# SCH__TX510__2025-04-04_-.net
KiCad netlist of a schematic drawn in Altium Designer
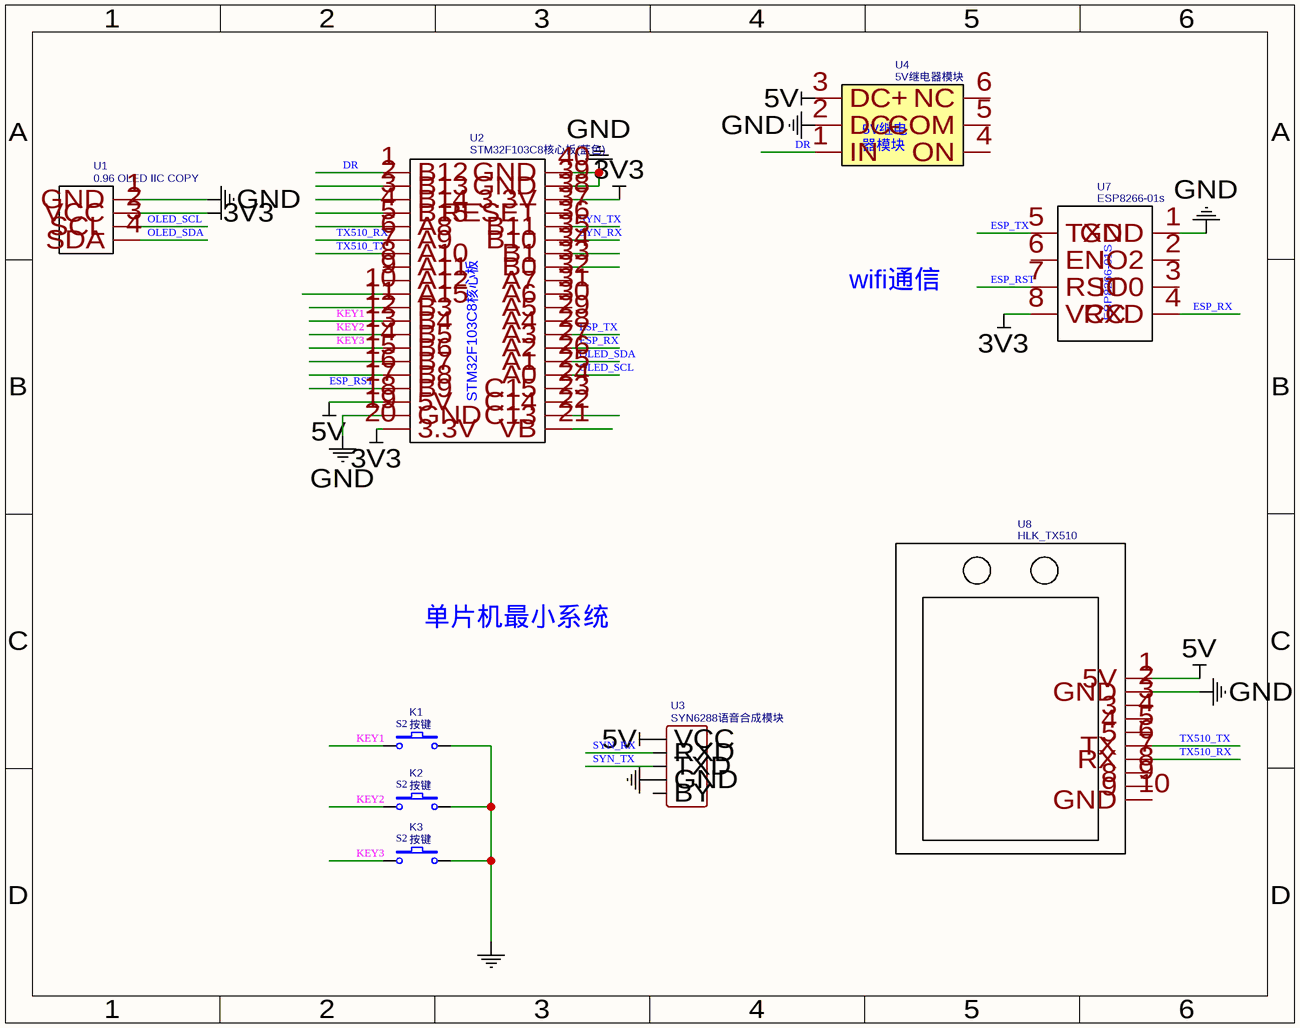
[diagram p0: SCH_人脸识别TX510和考勤_2025-04-04 - 副本.schdoc]

(export (version "E")
  (design (tool "Eeschema 10.0.6"))
  (components
    (comp (ref "K1")
      (value "按键")
      (fields (field (name "CONTRIBUTOR") "tongtongll"))
      (libsource (lib "altium-import") (part "root_1_按键_"))
    )
    (comp (ref "K2")
      (value "按键")
      (fields (field (name "CONTRIBUTOR") "tongtongll"))
      (libsource (lib "altium-import") (part "root_1_按键_"))
    )
    (comp (ref "K3")
      (value "按键")
      (fields (field (name "CONTRIBUTOR") "tongtongll"))
      (libsource (lib "altium-import") (part "root_1_按键_"))
    )
    (comp (ref "U1")
      (value "0.96 OLED IIC COPY")
      (fields (field (name "CONTRIBUTOR") "0errors0warning"))
      (libsource (lib "altium-import") (part "root_0_0.96 OLED IIC COPY_"))
    )
    (comp (ref "U2")
      (value "STM32F103C8核心板(蓝色)")
      (fields (field (name "CONTRIBUTOR") "JINZH"))
      (libsource (lib "altium-import") (part "root_0_STM32F103C8核心板(蓝色)_"))
    )
    (comp (ref "U3")
      (value "SYN6288语音合成模块")
      (fields (field (name "CONTRIBUTOR") "qq757683348"))
      (libsource (lib "altium-import") (part "root_0_SYN6288语音合成模块_"))
    )
    (comp (ref "U4")
      (value "5V继电器模块")
      (fields (field (name "CONTRIBUTOR") "zxt_esp8266"))
      (libsource (lib "altium-import") (part "root_2_5V继电器模块_"))
    )
    (comp (ref "U7")
      (value "ESP8266-01s")
      (fields (field (name "CONTRIBUTOR") "weidu"))
      (libsource (lib "altium-import") (part "root_3_ESP8266-01s_"))
    )
    (comp (ref "U8")
      (value "HLK_TX510")
      (fields (field (name "CONTRIBUTOR") "flyinglab"))
      (libsource (lib "altium-import") (part "root_0_HLK_TX510_"))
    )
  )
  (nets
    (net (code "1") (name "/DR") (class "Default")
      (node (ref "U2") (pin "1") (pinfunction "B12_1") (pintype "passive"))
      (node (ref "U4") (pin "1") (pinfunction "IN_1") (pintype "passive"))
    )
    (net (code "2") (name "/ESP_RST") (class "Default")
      (node (ref "U2") (pin "17") (pinfunction "B9_17") (pintype "passive"))
      (node (ref "U7") (pin "7") (pinfunction "RST_7") (pintype "passive"))
    )
    (net (code "3") (name "/ESP_RX") (class "Default")
      (node (ref "U2") (pin "27") (pinfunction "A2_27") (pintype "passive"))
      (node (ref "U7") (pin "4") (pinfunction "RXD_4") (pintype "passive"))
    )
    (net (code "4") (name "/ESP_TX") (class "Default")
      (node (ref "U2") (pin "28") (pinfunction "A3_28") (pintype "passive"))
      (node (ref "U7") (pin "5") (pinfunction "TXD_5") (pintype "passive"))
    )
    (net (code "5") (name "/KEY1") (class "Default")
      (node (ref "K1") (pin "1") (pinfunction "1_1") (pintype "passive"))
      (node (ref "U2") (pin "12") (pinfunction "B4_12") (pintype "passive"))
    )
    (net (code "6") (name "/KEY2") (class "Default")
      (node (ref "K2") (pin "1") (pinfunction "1_1") (pintype "passive"))
      (node (ref "U2") (pin "13") (pinfunction "B5_13") (pintype "passive"))
    )
    (net (code "7") (name "/KEY3") (class "Default")
      (node (ref "K3") (pin "1") (pinfunction "1_1") (pintype "passive"))
      (node (ref "U2") (pin "14") (pinfunction "B6_14") (pintype "passive"))
    )
    (net (code "8") (name "/OLED_SCL") (class "Default")
      (node (ref "U1") (pin "3") (pinfunction "SCL_3") (pintype "passive"))
      (node (ref "U2") (pin "25") (pinfunction "A0_25") (pintype "passive"))
    )
    (net (code "9") (name "/OLED_SDA") (class "Default")
      (node (ref "U1") (pin "4") (pinfunction "SDA_4") (pintype "passive"))
      (node (ref "U2") (pin "26") (pinfunction "A1_26") (pintype "passive"))
    )
    (net (code "10") (name "/SYN_RX") (class "Default")
      (node (ref "U2") (pin "35") (pinfunction "B10_35") (pintype "passive"))
      (node (ref "U3") (pin "2") (pinfunction "RXD_2") (pintype "passive"))
    )
    (net (code "11") (name "/SYN_TX") (class "Default")
      (node (ref "U2") (pin "36") (pinfunction "B11_36") (pintype "passive"))
      (node (ref "U3") (pin "3") (pinfunction "TXD_3") (pintype "passive"))
    )
    (net (code "12") (name "/TX510_RX") (class "Default")
      (node (ref "U2") (pin "6") (pinfunction "A9_6") (pintype "passive"))
      (node (ref "U8") (pin "7") (pinfunction "RX_7") (pintype "passive"))
    )
    (net (code "13") (name "/TX510_TX") (class "Default")
      (node (ref "U2") (pin "7") (pinfunction "A10_7") (pintype "passive"))
      (node (ref "U8") (pin "6") (pinfunction "TX_6") (pintype "passive"))
    )
    (net (code "14") (name "3V3") (class "Default")
      (node (ref "U1") (pin "2") (pinfunction "VCC_2") (pintype "passive"))
      (node (ref "U2") (pin "20") (pinfunction "3.3V_20") (pintype "passive"))
      (node (ref "U2") (pin "38") (pinfunction "3.3V_38") (pintype "passive"))
      (node (ref "U7") (pin "8") (pinfunction "VCC_8") (pintype "passive"))
    )
    (net (code "15") (name "5V") (class "Default")
      (node (ref "U2") (pin "18") (pinfunction "5V_18") (pintype "passive"))
      (node (ref "U3") (pin "1") (pinfunction "VCC_1") (pintype "passive"))
      (node (ref "U4") (pin "3") (pinfunction "DC+_3") (pintype "passive"))
      (node (ref "U8") (pin "1") (pinfunction "5V_1") (pintype "passive"))
    )
    (net (code "16") (name "GND") (class "Default")
      (node (ref "K1") (pin "3") (pinfunction "3_3") (pintype "passive"))
      (node (ref "K2") (pin "3") (pinfunction "3_3") (pintype "passive"))
      (node (ref "K3") (pin "3") (pinfunction "3_3") (pintype "passive"))
      (node (ref "U1") (pin "1") (pinfunction "GND_1") (pintype "passive"))
      (node (ref "U2") (pin "19") (pinfunction "GND_19") (pintype "passive"))
      (node (ref "U2") (pin "39") (pinfunction "GND_39") (pintype "passive"))
      (node (ref "U2") (pin "40") (pinfunction "GND_40") (pintype "passive"))
      (node (ref "U3") (pin "4") (pinfunction "GND_4") (pintype "passive"))
      (node (ref "U4") (pin "2") (pinfunction "DC-_2") (pintype "passive"))
      (node (ref "U7") (pin "1") (pinfunction "GND_1") (pintype "passive"))
      (node (ref "U8") (pin "2") (pinfunction "GND_2") (pintype "passive"))
    )
    (net (code "17") (name "unconnected-(U2-A4-Pad29)") (class "Default")
      (node (ref "U2") (pin "29") (pinfunction "A4_29") (pintype "passive"))
    )
    (net (code "18") (name "unconnected-(U2-A5-Pad30)") (class "Default")
      (node (ref "U2") (pin "30") (pinfunction "A5_30") (pintype "passive"))
    )
    (net (code "19") (name "unconnected-(U2-A6-Pad31)") (class "Default")
      (node (ref "U2") (pin "31") (pinfunction "A6_31") (pintype "passive"))
    )
    (net (code "20") (name "unconnected-(U2-A7-Pad32)") (class "Default")
      (node (ref "U2") (pin "32") (pinfunction "A7_32") (pintype "passive"))
    )
    (net (code "21") (name "unconnected-(U2-A8-Pad5)") (class "Default")
      (node (ref "U2") (pin "5") (pinfunction "A8_5") (pintype "passive"))
    )
    (net (code "22") (name "unconnected-(U2-A11-Pad8)") (class "Default")
      (node (ref "U2") (pin "8") (pinfunction "A11_8") (pintype "passive"))
    )
    (net (code "23") (name "unconnected-(U2-A12-Pad9)") (class "Default")
      (node (ref "U2") (pin "9") (pinfunction "A12_9") (pintype "passive"))
    )
    (net (code "24") (name "unconnected-(U2-A15-Pad10)") (class "Default")
      (node (ref "U2") (pin "10") (pinfunction "A15_10") (pintype "passive"))
    )
    (net (code "25") (name "unconnected-(U2-B0-Pad33)") (class "Default")
      (node (ref "U2") (pin "33") (pinfunction "B0_33") (pintype "passive"))
    )
    (net (code "26") (name "unconnected-(U2-B1-Pad34)") (class "Default")
      (node (ref "U2") (pin "34") (pinfunction "B1_34") (pintype "passive"))
    )
    (net (code "27") (name "unconnected-(U2-B3-Pad11)") (class "Default")
      (node (ref "U2") (pin "11") (pinfunction "B3_11") (pintype "passive"))
    )
    (net (code "28") (name "unconnected-(U2-B7-Pad15)") (class "Default")
      (node (ref "U2") (pin "15") (pinfunction "B7_15") (pintype "passive"))
    )
    (net (code "29") (name "unconnected-(U2-B8-Pad16)") (class "Default")
      (node (ref "U2") (pin "16") (pinfunction "B8_16") (pintype "passive"))
    )
    (net (code "30") (name "unconnected-(U2-B13-Pad2)") (class "Default")
      (node (ref "U2") (pin "2") (pinfunction "B13_2") (pintype "passive"))
    )
    (net (code "31") (name "unconnected-(U2-B14-Pad3)") (class "Default")
      (node (ref "U2") (pin "3") (pinfunction "B14_3") (pintype "passive"))
    )
    (net (code "32") (name "unconnected-(U2-B15-Pad4)") (class "Default")
      (node (ref "U2") (pin "4") (pinfunction "B15_4") (pintype "passive"))
    )
    (net (code "33") (name "unconnected-(U2-C13-Pad22)") (class "Default")
      (node (ref "U2") (pin "22") (pinfunction "C13_22") (pintype "passive"))
    )
    (net (code "34") (name "unconnected-(U2-C14-Pad23)") (class "Default")
      (node (ref "U2") (pin "23") (pinfunction "C14_23") (pintype "passive"))
    )
    (net (code "35") (name "unconnected-(U2-C15-Pad24)") (class "Default")
      (node (ref "U2") (pin "24") (pinfunction "C15_24") (pintype "passive"))
    )
    (net (code "36") (name "unconnected-(U2-RESET-Pad37)") (class "Default")
      (node (ref "U2") (pin "37") (pinfunction "RESET_37") (pintype "passive"))
    )
    (net (code "37") (name "unconnected-(U2-VB-Pad21)") (class "Default")
      (node (ref "U2") (pin "21") (pinfunction "VB_21") (pintype "passive"))
    )
    (net (code "38") (name "unconnected-(U3-BY-Pad5)") (class "Default")
      (node (ref "U3") (pin "5") (pinfunction "BY_5") (pintype "passive"))
    )
    (net (code "39") (name "unconnected-(U4-COM-Pad5)") (class "Default")
      (node (ref "U4") (pin "5") (pinfunction "COM_5") (pintype "passive"))
    )
    (net (code "40") (name "unconnected-(U4-NC-Pad6)") (class "Default")
      (node (ref "U4") (pin "6") (pinfunction "NC_6") (pintype "passive"))
    )
    (net (code "41") (name "unconnected-(U4-ON-Pad4)") (class "Default")
      (node (ref "U4") (pin "4") (pinfunction "ON_4") (pintype "passive"))
    )
    (net (code "42") (name "unconnected-(U7-EN-Pad6)") (class "Default")
      (node (ref "U7") (pin "6") (pinfunction "EN_6") (pintype "passive"))
    )
    (net (code "43") (name "unconnected-(U7-IO0-Pad3)") (class "Default")
      (node (ref "U7") (pin "3") (pinfunction "IO0_3") (pintype "passive"))
    )
    (net (code "44") (name "unconnected-(U7-IO2-Pad2)") (class "Default")
      (node (ref "U7") (pin "2") (pinfunction "IO2_2") (pintype "passive"))
    )
    (net (code "45") (name "unconnected-(U8-GND-Pad10)") (class "Default")
      (node (ref "U8") (pin "10") (pinfunction "GND_10") (pintype "passive"))
    )
    (net (code "46") (name "unconnected-(U8-Pad3)") (class "Default")
      (node (ref "U8") (pin "3") (pinfunction "3_3") (pintype "passive"))
    )
    (net (code "47") (name "unconnected-(U8-Pad4)") (class "Default")
      (node (ref "U8") (pin "4") (pinfunction "4_4") (pintype "passive"))
    )
    (net (code "48") (name "unconnected-(U8-Pad5)") (class "Default")
      (node (ref "U8") (pin "5") (pinfunction "5_5") (pintype "passive"))
    )
    (net (code "49") (name "unconnected-(U8-Pad8)") (class "Default")
      (node (ref "U8") (pin "8") (pinfunction "8_8") (pintype "passive"))
    )
    (net (code "50") (name "unconnected-(U8-Pad9)") (class "Default")
      (node (ref "U8") (pin "9") (pinfunction "9_9") (pintype "passive"))
    )
  )
)
